# Microcontroller.net
KiCad netlist of a schematic drawn in Altium Designer
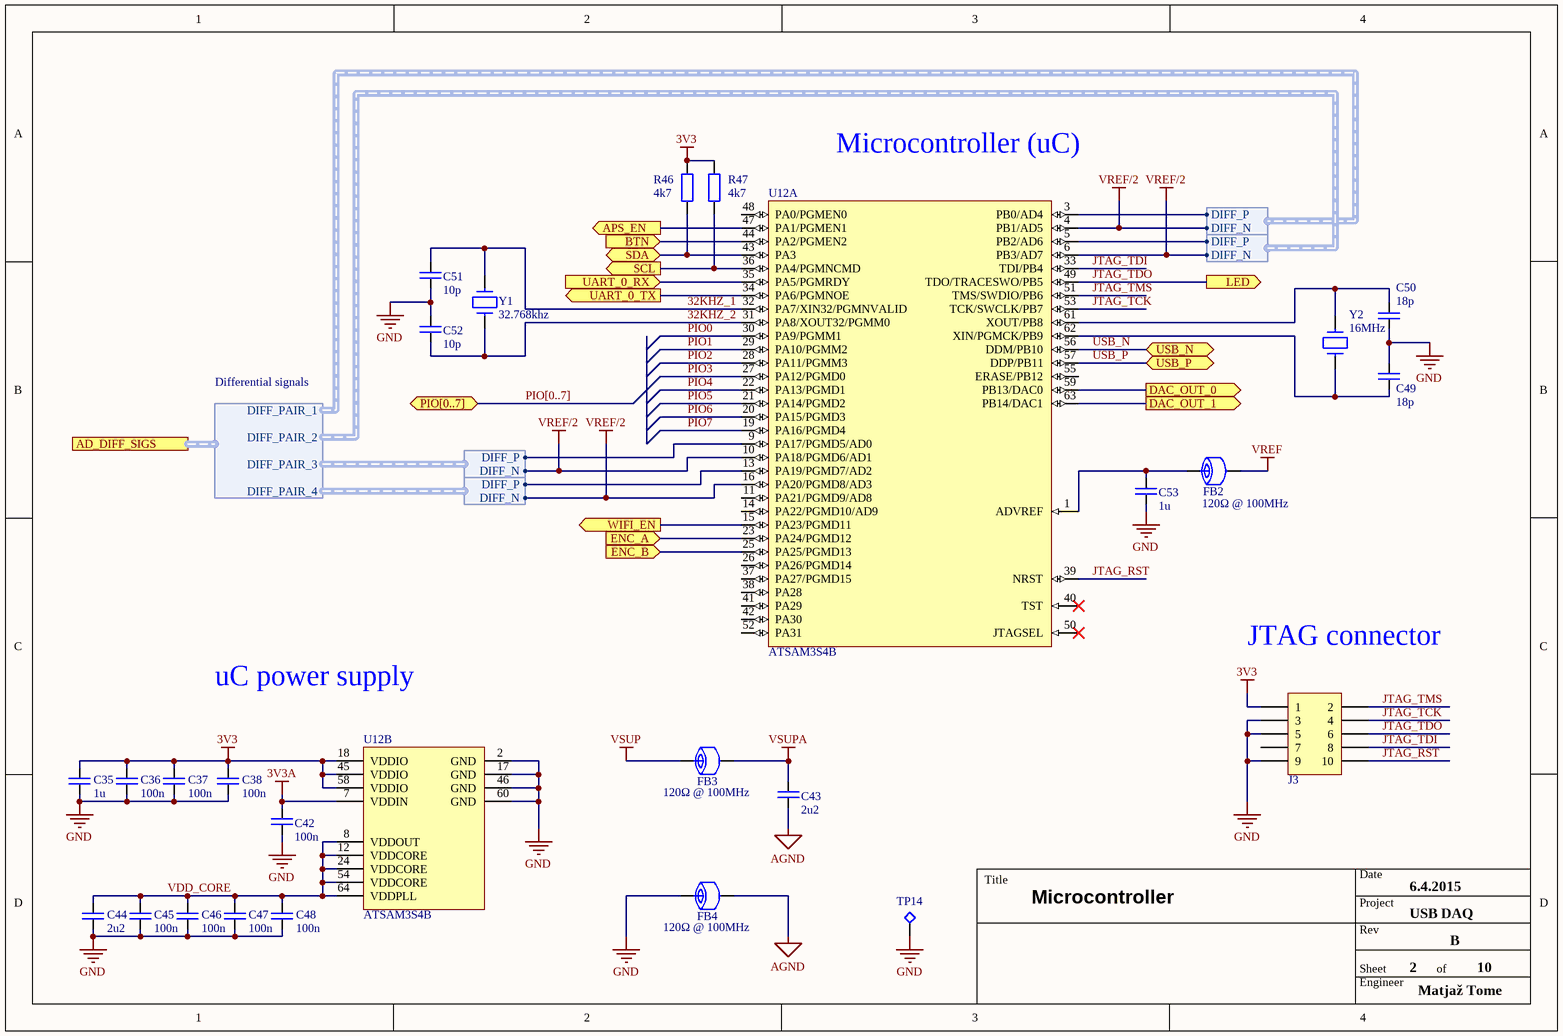
[diagram p0: Microcontroller.SchDoc]

(export (version "E")
  (design (tool "Eeschema 10.0.6"))
  (components
    (comp (ref "C35")
      (value "1u")
      (footprint "C_0603")
      (description "Generic capacitor")
      (libsource (lib "DAQ_REV_B") (part "Capacitor"))
    )
    (comp (ref "C36")
      (value "100n")
      (footprint "C_0603")
      (description "Generic capacitor")
      (libsource (lib "DAQ_REV_B") (part "Capacitor"))
    )
    (comp (ref "C37")
      (value "100n")
      (footprint "C_0603")
      (description "Generic capacitor")
      (libsource (lib "DAQ_REV_B") (part "Capacitor"))
    )
    (comp (ref "C38")
      (value "100n")
      (footprint "C_0603")
      (description "Generic capacitor")
      (libsource (lib "DAQ_REV_B") (part "Capacitor"))
    )
    (comp (ref "C42")
      (value "100n")
      (footprint "C_0603")
      (description "Generic capacitor")
      (libsource (lib "DAQ_REV_B") (part "Capacitor"))
    )
    (comp (ref "C43")
      (value "2u2")
      (footprint "C_0603")
      (description "Generic capacitor")
      (libsource (lib "DAQ_REV_B") (part "Capacitor"))
    )
    (comp (ref "C44")
      (value "2u2")
      (footprint "C_0603")
      (description "Generic capacitor")
      (libsource (lib "DAQ_REV_B") (part "Capacitor"))
    )
    (comp (ref "C45")
      (value "100n")
      (footprint "C_0603")
      (description "Generic capacitor")
      (libsource (lib "DAQ_REV_B") (part "Capacitor"))
    )
    (comp (ref "C46")
      (value "100n")
      (footprint "C_0603")
      (description "Generic capacitor")
      (libsource (lib "DAQ_REV_B") (part "Capacitor"))
    )
    (comp (ref "C47")
      (value "100n")
      (footprint "C_0603")
      (description "Generic capacitor")
      (libsource (lib "DAQ_REV_B") (part "Capacitor"))
    )
    (comp (ref "C48")
      (value "100n")
      (footprint "C_0603")
      (description "Generic capacitor")
      (libsource (lib "DAQ_REV_B") (part "Capacitor"))
    )
    (comp (ref "C49")
      (value "18p")
      (footprint "C_0603")
      (description "Generic capacitor")
      (libsource (lib "DAQ_REV_B") (part "Capacitor"))
    )
    (comp (ref "C50")
      (value "18p")
      (footprint "C_0603")
      (description "Generic capacitor")
      (libsource (lib "DAQ_REV_B") (part "Capacitor"))
    )
    (comp (ref "C51")
      (value "10p")
      (footprint "C_0603")
      (description "Generic capacitor")
      (libsource (lib "DAQ_REV_B") (part "Capacitor"))
    )
    (comp (ref "C52")
      (value "10p")
      (footprint "C_0603")
      (description "Generic capacitor")
      (libsource (lib "DAQ_REV_B") (part "Capacitor"))
    )
    (comp (ref "C53")
      (value "1u")
      (footprint "C_0603")
      (description "Generic capacitor")
      (libsource (lib "DAQ_REV_B") (part "Capacitor"))
    )
    (comp (ref "FB2")
      (value "120Ω @ 100MHz")
      (footprint "SMD_0805")
      (description "Ferrite Bead, 0805 [2012 Metric], 120 ohm, 800 mA, BLM21A Series, 0.15 ohm, ± 25%")
      (fields (field (name "MANUFACTURER") "Murata"))
      (libsource (lib "DAQ_REV_B") (part "BLM21AG121SN1D"))
    )
    (comp (ref "FB3")
      (value "120Ω @ 100MHz")
      (footprint "SMD_0805")
      (description "Ferrite Bead, 0805 [2012 Metric], 120 ohm, 800 mA, BLM21A Series, 0.15 ohm, ± 25%")
      (fields (field (name "MANUFACTURER") "Murata"))
      (libsource (lib "DAQ_REV_B") (part "BLM21AG121SN1D"))
    )
    (comp (ref "FB4")
      (value "120Ω @ 100MHz")
      (footprint "SMD_0805")
      (description "Ferrite Bead, 0805 [2012 Metric], 120 ohm, 800 mA, BLM21A Series, 0.15 ohm, ± 25%")
      (fields (field (name "MANUFACTURER") "Murata"))
      (libsource (lib "DAQ_REV_B") (part "BLM21AG121SN1D"))
    )
    (comp (ref "J3")
      (value "M50-3600542")
      (footprint "HEADER_2X05_1.27mm")
      (description "Pin Header, Board-to-Board, 1.27 mm, 2 Rows, 10 Contacts, Surface Mount, Archer M50 Series")
      (fields (field (name "MANUFACTURER") "Harwin"))
      (libsource (lib "DAQ_REV_B") (part "M50-3600542"))
    )
    (comp (ref "R46")
      (value "4k7")
      (footprint "R_0603")
      (description "Generic resistor")
      (libsource (lib "DAQ_REV_B") (part "Resistor"))
    )
    (comp (ref "R47")
      (value "4k7")
      (footprint "R_0603")
      (description "Generic resistor")
      (libsource (lib "DAQ_REV_B") (part "Resistor"))
    )
    (comp (ref "TP14")
      (value "testpoint")
      (footprint "TP1_FULL")
      (description "testpoint 1.5mm diameter no hole")
      (fields (field (name "PART NUMBER") "XXC0006"))
      (libsource (lib "DAQ_REV_B") (part "Test Point"))
    )
    (comp (ref "U12")
      (value "ATSAM3S4B")
      (footprint "LQFP64")
      (description "Cortex M3 ARM microcontroller")
      (fields (field (name "PART NUMBER") "XAM0003") (field (name "MANUFACTURER") "Atmel"))
      (libsource (lib "DAQ_REV_B") (part "ATSAM3SXB"))
    )
    (comp (ref "Y1")
      (value "32.768khz")
      (footprint "2X6_FLAT")
      (description "Crystal, 32.768 kHz, Cylinder Radial, 6.2mm x 2mm Dia, 12.5 pF, 20 ppm, R26 Series")
      (fields (field (name "PART NUMBER") "XCR0010") (field (name "MANUFACTURER") "RALTRON"))
      (libsource (lib "DAQ_REV_B") (part "R26-32.768- 12.5"))
    )
    (comp (ref "Y2")
      (value "16MHz")
      (footprint "5X3.2")
      (description "Crystal, 16 MHz, SMD, 5mm x 3.2mm, 30 ppm, 18 pF, 30 ppm, 7A Series")
      (fields (field (name "MANUFACTURER") "TCX"))
      (libsource (lib "DAQ_REV_B") (part "7A-16.000MAAJ-T"))
    )
  )
  (nets
    (net (code "5") (name "/32KHZ_1") (class "Default")
      (node (ref "C51") (pin "1") (pinfunction "1_1") (pintype "passive"))
      (node (ref "U12") (pin "32") (pinfunction "PA7/XIN32/PGMNVALID_32") (pintype "bidirectional"))
      (node (ref "Y1") (pin "2") (pinfunction "2_2") (pintype "passive"))
    )
    (net (code "6") (name "/32KHZ_2") (class "Default")
      (node (ref "C52") (pin "1") (pinfunction "1_1") (pintype "passive"))
      (node (ref "U12") (pin "31") (pinfunction "PA8/XOUT32/PGMM0_31") (pintype "bidirectional"))
      (node (ref "Y1") (pin "1") (pinfunction "1_1") (pintype "passive"))
    )
    (net (code "8") (name "/APS_EN") (class "Default")
      (node (ref "U12") (pin "47") (pinfunction "PA1/PGMEN1_47") (pintype "bidirectional"))
    )
    (net (code "9") (name "/BTN") (class "Default")
      (node (ref "U12") (pin "44") (pinfunction "PA2/PGMEN2_44") (pintype "bidirectional"))
    )
    (net (code "10") (name "/DAC_OUT_0") (class "Default")
      (node (ref "U12") (pin "59") (pinfunction "PB13/DAC0_59") (pintype "bidirectional"))
    )
    (net (code "11") (name "/DAC_OUT_1") (class "Default")
      (node (ref "U12") (pin "63") (pinfunction "PB14/DAC1_63") (pintype "bidirectional"))
    )
    (net (code "12") (name "/ENC_A") (class "Default")
      (node (ref "U12") (pin "23") (pinfunction "PA24/PGMD12_23") (pintype "bidirectional"))
    )
    (net (code "13") (name "/ENC_B") (class "Default")
      (node (ref "U12") (pin "25") (pinfunction "PA25/PGMD13_25") (pintype "bidirectional"))
    )
    (net (code "14") (name "/JTAG_RST") (class "Default")
      (node (ref "J3") (pin "10") (pinfunction "10_10") (pintype "passive"))
      (node (ref "U12") (pin "39") (pinfunction "NRST_39") (pintype "bidirectional"))
    )
    (net (code "15") (name "/JTAG_TCK") (class "Default")
      (node (ref "J3") (pin "4") (pinfunction "4_4") (pintype "passive"))
      (node (ref "U12") (pin "53") (pinfunction "TCK/SWCLK/PB7_53") (pintype "bidirectional"))
    )
    (net (code "16") (name "/JTAG_TDI") (class "Default")
      (node (ref "J3") (pin "8") (pinfunction "8_8") (pintype "passive"))
      (node (ref "U12") (pin "33") (pinfunction "TDI/PB4_33") (pintype "bidirectional"))
    )
    (net (code "17") (name "/JTAG_TDO") (class "Default")
      (node (ref "J3") (pin "6") (pinfunction "6_6") (pintype "passive"))
      (node (ref "U12") (pin "49") (pinfunction "TDO/TRACESWO/PB5_49") (pintype "bidirectional"))
    )
    (net (code "18") (name "/JTAG_TMS") (class "Default")
      (node (ref "J3") (pin "2") (pinfunction "2_2") (pintype "passive"))
      (node (ref "U12") (pin "51") (pinfunction "TMS/SWDIO/PB6_51") (pintype "bidirectional"))
    )
    (net (code "19") (name "/PIO0") (class "Default")
      (node (ref "U12") (pin "30") (pinfunction "PA9/PGMM1_30") (pintype "bidirectional"))
    )
    (net (code "20") (name "/PIO1") (class "Default")
      (node (ref "U12") (pin "29") (pinfunction "PA10/PGMM2_29") (pintype "bidirectional"))
    )
    (net (code "21") (name "/PIO2") (class "Default")
      (node (ref "U12") (pin "28") (pinfunction "PA11/PGMM3_28") (pintype "bidirectional"))
    )
    (net (code "22") (name "/PIO3") (class "Default")
      (node (ref "U12") (pin "27") (pinfunction "PA12/PGMD0_27") (pintype "bidirectional"))
    )
    (net (code "23") (name "/PIO4") (class "Default")
      (node (ref "U12") (pin "22") (pinfunction "PA13/PGMD1_22") (pintype "bidirectional"))
    )
    (net (code "24") (name "/PIO5") (class "Default")
      (node (ref "U12") (pin "21") (pinfunction "PA14/PGMD2_21") (pintype "bidirectional"))
    )
    (net (code "25") (name "/PIO6") (class "Default")
      (node (ref "U12") (pin "20") (pinfunction "PA15/PGMD3_20") (pintype "bidirectional"))
    )
    (net (code "26") (name "/PIO7") (class "Default")
      (node (ref "U12") (pin "19") (pinfunction "PA16/PGMD4_19") (pintype "bidirectional"))
    )
    (net (code "28") (name "/SCL") (class "Default")
      (node (ref "R47") (pin "1") (pintype "passive"))
      (node (ref "U12") (pin "36") (pinfunction "PA4/PGMNCMD_36") (pintype "bidirectional"))
    )
    (net (code "29") (name "/SDA") (class "Default")
      (node (ref "R46") (pin "1") (pintype "passive"))
      (node (ref "U12") (pin "43") (pinfunction "PA3_43") (pintype "bidirectional"))
    )
    (net (code "30") (name "/UART_0_RX") (class "Default")
      (node (ref "U12") (pin "35") (pinfunction "PA5/PGMRDY_35") (pintype "bidirectional"))
    )
    (net (code "31") (name "/UART_0_TX") (class "Default")
      (node (ref "U12") (pin "34") (pinfunction "PA6/PGMNOE_34") (pintype "bidirectional"))
    )
    (net (code "32") (name "/USB_N") (class "Default")
      (node (ref "U12") (pin "56") (pinfunction "DDM/PB10_56") (pintype "bidirectional"))
    )
    (net (code "33") (name "/USB_P") (class "Default")
      (node (ref "U12") (pin "57") (pinfunction "DDP/PB11_57") (pintype "bidirectional"))
    )
    (net (code "34") (name "/VDD_CORE") (class "Default")
      (node (ref "C44") (pin "1") (pinfunction "1_1") (pintype "passive"))
      (node (ref "C45") (pin "1") (pinfunction "1_1") (pintype "passive"))
      (node (ref "C46") (pin "1") (pinfunction "1_1") (pintype "passive"))
      (node (ref "C47") (pin "1") (pinfunction "1_1") (pintype "passive"))
      (node (ref "C48") (pin "1") (pinfunction "1_1") (pintype "passive"))
      (node (ref "U12") (pin "12") (pinfunction "VDDCORE_12") (pintype "power_in"))
      (node (ref "U12") (pin "24") (pinfunction "VDDCORE_24") (pintype "power_in"))
      (node (ref "U12") (pin "54") (pinfunction "VDDCORE_54") (pintype "power_in"))
      (node (ref "U12") (pin "64") (pinfunction "VDDPLL_64") (pintype "power_in"))
      (node (ref "U12") (pin "8") (pinfunction "VDDOUT_8") (pintype "power_in"))
    )
    (net (code "35") (name "/WIFI_EN") (class "Default")
      (node (ref "U12") (pin "15") (pinfunction "PA23/PGMD11_15") (pintype "bidirectional"))
    )
    (net (code "37") (name "3V3") (class "Default")
      (node (ref "C35") (pin "1") (pinfunction "1_1") (pintype "passive"))
      (node (ref "C36") (pin "1") (pinfunction "1_1") (pintype "passive"))
      (node (ref "C37") (pin "1") (pinfunction "1_1") (pintype "passive"))
      (node (ref "C38") (pin "1") (pinfunction "1_1") (pintype "passive"))
      (node (ref "J3") (pin "1") (pinfunction "1_1") (pintype "passive"))
      (node (ref "R46") (pin "2") (pintype "passive"))
      (node (ref "R47") (pin "2") (pintype "passive"))
      (node (ref "U12") (pin "18") (pinfunction "VDDIO_18") (pintype "power_in"))
      (node (ref "U12") (pin "45") (pinfunction "VDDIO_45") (pintype "power_in"))
      (node (ref "U12") (pin "58") (pinfunction "VDDIO_58") (pintype "power_in"))
    )
    (net (code "38") (name "3V3A") (class "Default")
      (node (ref "C42") (pin "1") (pinfunction "1_1") (pintype "passive"))
      (node (ref "U12") (pin "7") (pinfunction "VDDIN_7") (pintype "power_in"))
    )
    (net (code "39") (name "AGND") (class "Default")
      (node (ref "C43") (pin "2") (pinfunction "2_2") (pintype "passive"))
      (node (ref "FB4") (pin "2") (pintype "passive"))
    )
    (net (code "40") (name "GND") (class "Default")
      (node (ref "C35") (pin "2") (pinfunction "2_2") (pintype "passive"))
      (node (ref "C36") (pin "2") (pinfunction "2_2") (pintype "passive"))
      (node (ref "C37") (pin "2") (pinfunction "2_2") (pintype "passive"))
      (node (ref "C38") (pin "2") (pinfunction "2_2") (pintype "passive"))
      (node (ref "C42") (pin "2") (pinfunction "2_2") (pintype "passive"))
      (node (ref "C44") (pin "2") (pinfunction "2_2") (pintype "passive"))
      (node (ref "C45") (pin "2") (pinfunction "2_2") (pintype "passive"))
      (node (ref "C46") (pin "2") (pinfunction "2_2") (pintype "passive"))
      (node (ref "C47") (pin "2") (pinfunction "2_2") (pintype "passive"))
      (node (ref "C48") (pin "2") (pinfunction "2_2") (pintype "passive"))
      (node (ref "C49") (pin "2") (pinfunction "2_2") (pintype "passive"))
      (node (ref "C50") (pin "2") (pinfunction "2_2") (pintype "passive"))
      (node (ref "C51") (pin "2") (pinfunction "2_2") (pintype "passive"))
      (node (ref "C52") (pin "2") (pinfunction "2_2") (pintype "passive"))
      (node (ref "C53") (pin "2") (pinfunction "2_2") (pintype "passive"))
      (node (ref "FB4") (pin "1") (pintype "passive"))
      (node (ref "J3") (pin "3") (pinfunction "3_3") (pintype "passive"))
      (node (ref "J3") (pin "5") (pinfunction "5_5") (pintype "passive"))
      (node (ref "J3") (pin "9") (pinfunction "9_9") (pintype "passive"))
      (node (ref "TP14") (pin "1") (pinfunction "1_1") (pintype "passive"))
      (node (ref "U12") (pin "17") (pinfunction "GND_17") (pintype "power_in"))
      (node (ref "U12") (pin "2") (pinfunction "GND_2") (pintype "power_in"))
      (node (ref "U12") (pin "46") (pinfunction "GND_46") (pintype "power_in"))
      (node (ref "U12") (pin "60") (pinfunction "GND_60") (pintype "power_in"))
    )
    (net (code "41") (name "Net-(U12A-ADVREF)") (class "Default")
      (node (ref "C53") (pin "1") (pinfunction "1_1") (pintype "passive"))
      (node (ref "FB2") (pin "1") (pintype "passive"))
      (node (ref "U12") (pin "1") (pinfunction "ADVREF_1") (pintype "input"))
    )
    (net (code "42") (name "Net-(U12A-XIN{slash}PGMCK{slash}PB9)") (class "Default")
      (node (ref "C49") (pin "1") (pinfunction "1_1") (pintype "passive"))
      (node (ref "U12") (pin "62") (pinfunction "XIN/PGMCK/PB9_62") (pintype "bidirectional"))
      (node (ref "Y2") (pin "1") (pinfunction "1_1") (pintype "passive"))
    )
    (net (code "43") (name "Net-(U12A-XOUT{slash}PB8)") (class "Default")
      (node (ref "C50") (pin "1") (pinfunction "1_1") (pintype "passive"))
      (node (ref "U12") (pin "61") (pinfunction "XOUT/PB8_61") (pintype "bidirectional"))
      (node (ref "Y2") (pin "2") (pinfunction "2_2") (pintype "passive"))
    )
    (net (code "44") (name "VREF") (class "Default") (node (ref "FB2") (pin "2") (pintype "passive")))
    (net (code "45") (name "VREF{slash}2") (class "Default")
      (node (ref "U12") (pin "10") (pinfunction "PA18/PGMD6/AD1_10") (pintype "bidirectional"))
      (node (ref "U12") (pin "16") (pinfunction "PA20/PGMD8/AD3_16") (pintype "bidirectional"))
      (node (ref "U12") (pin "4") (pinfunction "PB1/AD5_4") (pintype "bidirectional"))
      (node (ref "U12") (pin "6") (pinfunction "PB3/AD7_6") (pintype "bidirectional"))
    )
    (net (code "46") (name "VSUP") (class "Default") (node (ref "FB3") (pin "1") (pintype "passive")))
    (net (code "47") (name "VSUPA") (class "Default")
      (node (ref "C43") (pin "1") (pinfunction "1_1") (pintype "passive"))
      (node (ref "FB3") (pin "2") (pintype "passive"))
    )
    (net (code "48") (name "unconnected-(J3-Pad7)") (class "Default")
      (node (ref "J3") (pin "7") (pinfunction "7_7") (pintype "passive"))
    )
    (net (code "49") (name "unconnected-(U12A-ERASE{slash}PB12-Pad55)") (class "Default")
      (node (ref "U12") (pin "55") (pinfunction "ERASE/PB12_55") (pintype "bidirectional"))
    )
    (net (code "50") (name "unconnected-(U12A-JTAGSEL-Pad50)") (class "Default")
      (node (ref "U12") (pin "50") (pinfunction "JTAGSEL_50") (pintype "input+no_connect"))
    )
    (net (code "51") (name "unconnected-(U12A-PA0{slash}PGMEN0-Pad48)") (class "Default")
      (node (ref "U12") (pin "48") (pinfunction "PA0/PGMEN0_48") (pintype "bidirectional"))
    )
    (net (code "52") (name "unconnected-(U12A-PA17{slash}PGMD5{slash}AD0-Pad9)") (class "Default")
      (node (ref "U12") (pin "9") (pinfunction "PA17/PGMD5/AD0_9") (pintype "bidirectional"))
    )
    (net (code "53") (name "unconnected-(U12A-PA19{slash}PGMD7{slash}AD2-Pad13)") (class "Default")
      (node (ref "U12") (pin "13") (pinfunction "PA19/PGMD7/AD2_13") (pintype "bidirectional"))
    )
    (net (code "54") (name "unconnected-(U12A-PA21{slash}PGMD9{slash}AD8-Pad11)") (class "Default")
      (node (ref "U12") (pin "11") (pinfunction "PA21/PGMD9/AD8_11") (pintype "bidirectional"))
    )
    (net (code "55") (name "unconnected-(U12A-PA22{slash}PGMD10{slash}AD9-Pad14)") (class "Default")
      (node (ref "U12") (pin "14") (pinfunction "PA22/PGMD10/AD9_14") (pintype "bidirectional"))
    )
    (net (code "56") (name "unconnected-(U12A-PA26{slash}PGMD14-Pad26)") (class "Default")
      (node (ref "U12") (pin "26") (pinfunction "PA26/PGMD14_26") (pintype "bidirectional"))
    )
    (net (code "57") (name "unconnected-(U12A-PA27{slash}PGMD15-Pad37)") (class "Default")
      (node (ref "U12") (pin "37") (pinfunction "PA27/PGMD15_37") (pintype "bidirectional"))
    )
    (net (code "58") (name "unconnected-(U12A-PA28-Pad38)") (class "Default")
      (node (ref "U12") (pin "38") (pinfunction "PA28_38") (pintype "bidirectional"))
    )
    (net (code "59") (name "unconnected-(U12A-PA29-Pad41)") (class "Default")
      (node (ref "U12") (pin "41") (pinfunction "PA29_41") (pintype "bidirectional"))
    )
    (net (code "60") (name "unconnected-(U12A-PA30-Pad42)") (class "Default")
      (node (ref "U12") (pin "42") (pinfunction "PA30_42") (pintype "bidirectional"))
    )
    (net (code "61") (name "unconnected-(U12A-PA31-Pad52)") (class "Default")
      (node (ref "U12") (pin "52") (pinfunction "PA31_52") (pintype "bidirectional"))
    )
    (net (code "62") (name "unconnected-(U12A-PB0{slash}AD4-Pad3)") (class "Default")
      (node (ref "U12") (pin "3") (pinfunction "PB0/AD4_3") (pintype "bidirectional"))
    )
    (net (code "63") (name "unconnected-(U12A-PB2{slash}AD6-Pad5)") (class "Default")
      (node (ref "U12") (pin "5") (pinfunction "PB2/AD6_5") (pintype "bidirectional"))
    )
    (net (code "64") (name "unconnected-(U12A-TST-Pad40)") (class "Default")
      (node (ref "U12") (pin "40") (pinfunction "TST_40") (pintype "input+no_connect"))
    )
  )
)
